# arduino_board.net
KiCad netlist of a schematic drawn in EAGLE
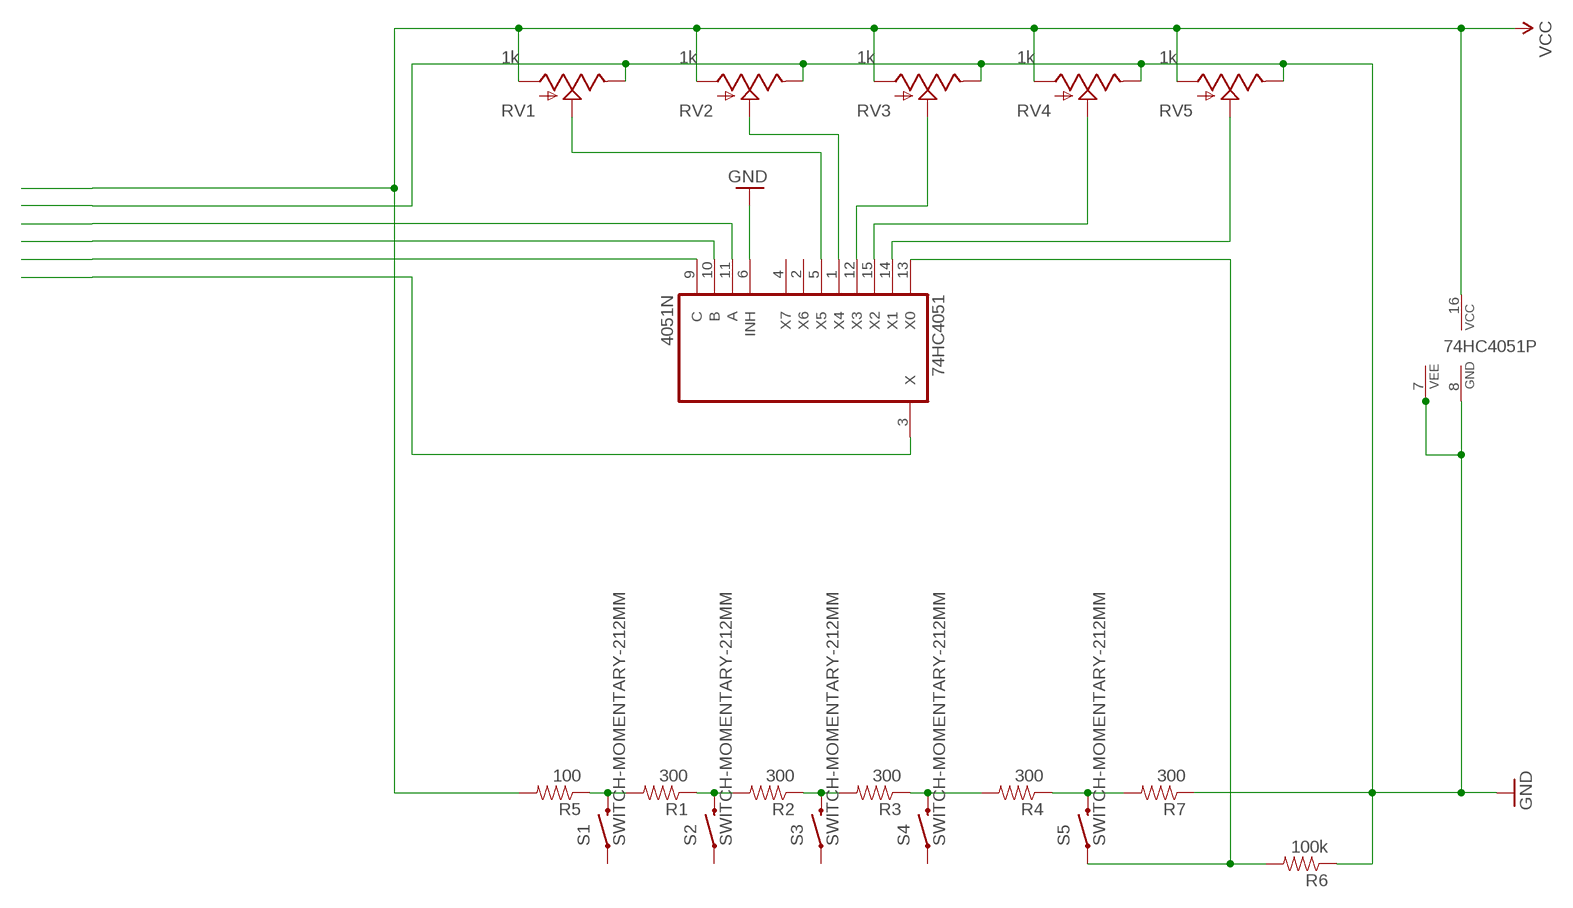
[diagram p0: schematic, sheet 1]
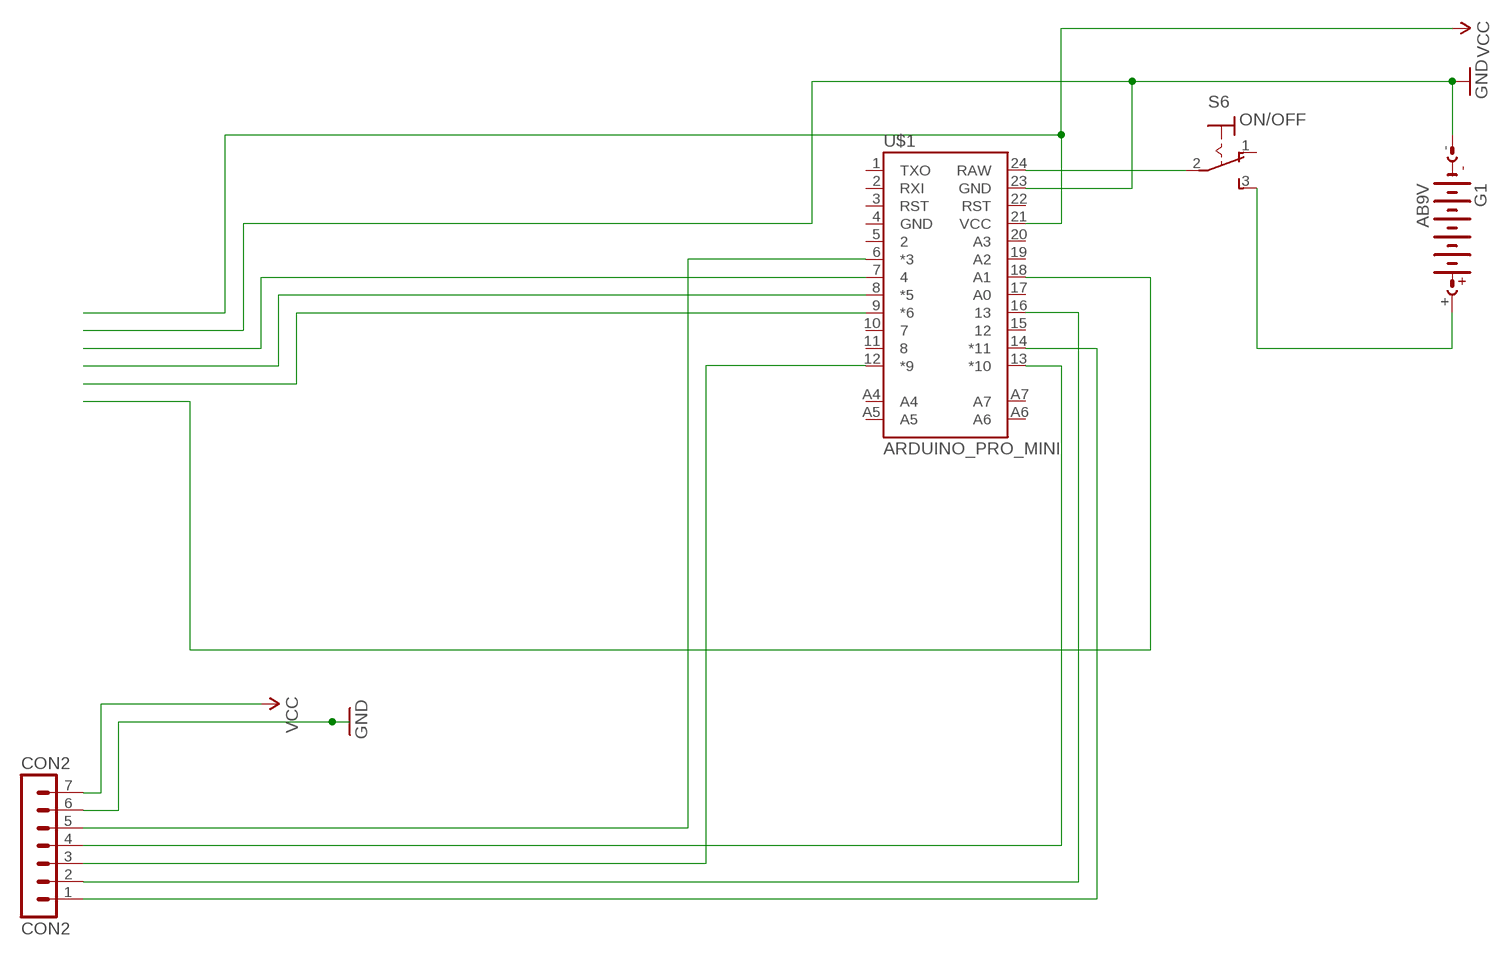
[diagram p1: schematic, sheet 2]

(export (version "E")
  (design (tool "Eeschema 10.0.6"))
  (components
    (comp (ref "CON2")
      (value "CON2")
      (footprint "eagle-import:MA07-1")
      (libsource (lib "eagle-import") (part "MA07-1"))
    )
    (comp (ref "G1")
      (value "AB9V")
      (footprint "eagle-import:AB9V")
      (libsource (lib "eagle-import") (part "AB9V"))
    )
    (comp (ref "S6")
      (value "ON/OFF")
      (footprint "eagle-import:320-916")
      (libsource (lib "eagle-import") (part "320-916"))
    )
    (comp (ref "U$1")
      (value "ARDUINO_PRO_MINI")
      (footprint "eagle-import:ARDUINO_PRO_MINI")
      (libsource (lib "eagle-import") (part "ARDUINO_PRO_MINI"))
    )
    (comp (ref "74HC4051")
      (value "4051N")
      (footprint "eagle-import:DIL16")
      (libsource (lib "eagle-import") (part "4051N"))
    )
    (comp (ref "R1")
      (value "300")
      (footprint "eagle-import:AXIAL-0.5")
      (libsource (lib "eagle-import") (part "RESISTORPTH-1/2W"))
    )
    (comp (ref "R2")
      (value "300")
      (footprint "eagle-import:AXIAL-0.5")
      (libsource (lib "eagle-import") (part "RESISTORPTH-1/2W"))
    )
    (comp (ref "R3")
      (value "300")
      (footprint "eagle-import:AXIAL-0.5")
      (libsource (lib "eagle-import") (part "RESISTORPTH-1/2W"))
    )
    (comp (ref "R4")
      (value "300")
      (footprint "eagle-import:AXIAL-0.5")
      (libsource (lib "eagle-import") (part "RESISTORPTH-1/2W"))
    )
    (comp (ref "R5")
      (value "100")
      (footprint "eagle-import:AXIAL-0.5")
      (libsource (lib "eagle-import") (part "RESISTORPTH-1/2W"))
    )
    (comp (ref "R6")
      (value "100k")
      (footprint "eagle-import:AXIAL-0.5")
      (libsource (lib "eagle-import") (part "RESISTORPTH-1/2W"))
    )
    (comp (ref "R7")
      (value "300")
      (footprint "eagle-import:AXIAL-0.5")
      (libsource (lib "eagle-import") (part "RESISTORPTH-1/2W"))
    )
    (comp (ref "RV1")
      (value "1k")
      (footprint "eagle-import:ALPS_POT")
      (libsource (lib "eagle-import") (part "POT"))
    )
    (comp (ref "RV2")
      (value "1k")
      (footprint "eagle-import:ALPS_POT")
      (libsource (lib "eagle-import") (part "POT"))
    )
    (comp (ref "RV3")
      (value "1k")
      (footprint "eagle-import:ALPS_POT")
      (libsource (lib "eagle-import") (part "POT"))
    )
    (comp (ref "RV4")
      (value "1k")
      (footprint "eagle-import:ALPS_POT")
      (libsource (lib "eagle-import") (part "POT"))
    )
    (comp (ref "RV5")
      (value "1k")
      (footprint "eagle-import:ALPS_POT")
      (libsource (lib "eagle-import") (part "POT"))
    )
    (comp (ref "S1")
      (value "SWITCH-MOMENTARY-212MM")
      (footprint "eagle-import:TACTILE-PTH-12MM")
      (libsource (lib "eagle-import") (part "SWITCH-MOMENTARY-212MM"))
    )
    (comp (ref "S2")
      (value "SWITCH-MOMENTARY-212MM")
      (footprint "eagle-import:TACTILE-PTH-12MM")
      (libsource (lib "eagle-import") (part "SWITCH-MOMENTARY-212MM"))
    )
    (comp (ref "S3")
      (value "SWITCH-MOMENTARY-212MM")
      (footprint "eagle-import:TACTILE-PTH-12MM")
      (libsource (lib "eagle-import") (part "SWITCH-MOMENTARY-212MM"))
    )
    (comp (ref "S4")
      (value "SWITCH-MOMENTARY-212MM")
      (footprint "eagle-import:TACTILE-PTH-12MM")
      (libsource (lib "eagle-import") (part "SWITCH-MOMENTARY-212MM"))
    )
    (comp (ref "S5")
      (value "SWITCH-MOMENTARY-212MM")
      (footprint "eagle-import:TACTILE-PTH-12MM")
      (libsource (lib "eagle-import") (part "SWITCH-MOMENTARY-212MM"))
    )
  )
  (nets
    (net (code "1") (name "A1") (class "Default")
      (node (ref "74HC4051") (pin "3") (pinfunction "X_3") (pintype "bidirectional"))
      (node (ref "U$1") (pin "18") (pinfunction "A1_18") (pintype "bidirectional"))
    )
    (net (code "2") (name "D4_A_S0") (class "Default")
      (node (ref "74HC4051") (pin "11") (pinfunction "A_11") (pintype "input"))
      (node (ref "U$1") (pin "7") (pinfunction "4_7") (pintype "bidirectional"))
    )
    (net (code "3") (name "D5_B_S1") (class "Default")
      (node (ref "74HC4051") (pin "10") (pinfunction "B_10") (pintype "input"))
      (node (ref "U$1") (pin "8") (pinfunction "*5_8") (pintype "bidirectional"))
    )
    (net (code "4") (name "D6_C_S2") (class "Default")
      (node (ref "74HC4051") (pin "9") (pinfunction "C_9") (pintype "input"))
      (node (ref "U$1") (pin "9") (pinfunction "*6_9") (pintype "bidirectional"))
    )
    (net (code "5") (name "GND") (class "Default")
      (node (ref "74HC4051") (pin "6") (pinfunction "INH_6") (pintype "input"))
      (node (ref "74HC4051") (pin "7") (pinfunction "VEE_7") (pintype "power_in"))
      (node (ref "74HC4051") (pin "8") (pinfunction "GND_8") (pintype "power_in"))
      (node (ref "CON2") (pin "6") (pinfunction "6_6") (pintype "passive"))
      (node (ref "G1") (pin "-") (pinfunction "-_-") (pintype "passive"))
      (node (ref "R6") (pin "P$1") (pinfunction "1_P$1") (pintype "passive"))
      (node (ref "R7") (pin "P$1") (pinfunction "1_P$1") (pintype "passive"))
      (node (ref "RV1") (pin "P$1") (pinfunction "E_P$1") (pintype "passive"))
      (node (ref "RV2") (pin "P$1") (pinfunction "E_P$1") (pintype "passive"))
      (node (ref "RV3") (pin "P$1") (pinfunction "E_P$1") (pintype "passive"))
      (node (ref "RV4") (pin "P$1") (pinfunction "E_P$1") (pintype "passive"))
      (node (ref "RV5") (pin "P$1") (pinfunction "E_P$1") (pintype "passive"))
      (node (ref "U$1") (pin "23") (pinfunction "GND_23") (pintype "bidirectional"))
    )
    (net (code "6") (name "Net-(74HC4051A-X0)") (class "Default")
      (node (ref "74HC4051") (pin "13") (pinfunction "X0_13") (pintype "bidirectional"))
      (node (ref "R6") (pin "P$2") (pinfunction "2_P$2") (pintype "passive"))
      (node (ref "S5") (pin "1") (pinfunction "1_1") (pintype "passive"))
    )
    (net (code "7") (name "Net-(74HC4051A-X1)") (class "Default")
      (node (ref "74HC4051") (pin "14") (pinfunction "X1_14") (pintype "bidirectional"))
      (node (ref "RV5") (pin "P$2") (pinfunction "S_P$2") (pintype "passive"))
    )
    (net (code "8") (name "Net-(74HC4051A-X2)") (class "Default")
      (node (ref "74HC4051") (pin "15") (pinfunction "X2_15") (pintype "bidirectional"))
      (node (ref "RV4") (pin "P$2") (pinfunction "S_P$2") (pintype "passive"))
    )
    (net (code "9") (name "Net-(74HC4051A-X3)") (class "Default")
      (node (ref "74HC4051") (pin "12") (pinfunction "X3_12") (pintype "bidirectional"))
      (node (ref "RV3") (pin "P$2") (pinfunction "S_P$2") (pintype "passive"))
    )
    (net (code "10") (name "Net-(74HC4051A-X4)") (class "Default")
      (node (ref "74HC4051") (pin "1") (pinfunction "X4_1") (pintype "bidirectional"))
      (node (ref "RV2") (pin "P$2") (pinfunction "S_P$2") (pintype "passive"))
    )
    (net (code "11") (name "Net-(74HC4051A-X5)") (class "Default")
      (node (ref "74HC4051") (pin "5") (pinfunction "X5_5") (pintype "bidirectional"))
      (node (ref "RV1") (pin "P$2") (pinfunction "S_P$2") (pintype "passive"))
    )
    (net (code "12") (name "Net-(R1-1)") (class "Default")
      (node (ref "R1") (pin "P$1") (pinfunction "1_P$1") (pintype "passive"))
      (node (ref "R2") (pin "P$2") (pinfunction "2_P$2") (pintype "passive"))
      (node (ref "S2") (pin "3") (pinfunction "2_3") (pintype "passive"))
    )
    (net (code "13") (name "Net-(R1-2)") (class "Default")
      (node (ref "R1") (pin "P$2") (pinfunction "2_P$2") (pintype "passive"))
      (node (ref "R5") (pin "P$1") (pinfunction "1_P$1") (pintype "passive"))
      (node (ref "S1") (pin "3") (pinfunction "2_3") (pintype "passive"))
    )
    (net (code "14") (name "Net-(R2-1)") (class "Default")
      (node (ref "R2") (pin "P$1") (pinfunction "1_P$1") (pintype "passive"))
      (node (ref "R3") (pin "P$2") (pinfunction "2_P$2") (pintype "passive"))
      (node (ref "S3") (pin "3") (pinfunction "2_3") (pintype "passive"))
    )
    (net (code "15") (name "Net-(R3-1)") (class "Default")
      (node (ref "R3") (pin "P$1") (pinfunction "1_P$1") (pintype "passive"))
      (node (ref "R4") (pin "P$2") (pinfunction "2_P$2") (pintype "passive"))
      (node (ref "S4") (pin "3") (pinfunction "2_3") (pintype "passive"))
    )
    (net (code "16") (name "Net-(R4-1)") (class "Default")
      (node (ref "R4") (pin "P$1") (pinfunction "1_P$1") (pintype "passive"))
      (node (ref "R7") (pin "P$2") (pinfunction "2_P$2") (pintype "passive"))
      (node (ref "S5") (pin "3") (pinfunction "2_3") (pintype "passive"))
    )
    (net (code "17") (name "Net-(S6-P)") (class "Default")
      (node (ref "S6") (pin "2") (pinfunction "P_2") (pintype "passive"))
      (node (ref "U$1") (pin "24") (pinfunction "RAW_24") (pintype "bidirectional"))
    )
    (net (code "18") (name "Net-(S6-S)") (class "Default")
      (node (ref "G1") (pin "+") (pinfunction "+_+") (pintype "passive"))
      (node (ref "S6") (pin "3") (pinfunction "S_3") (pintype "passive"))
    )
    (net (code "19") (name "Net-(U$1-*3)") (class "Default")
      (node (ref "CON2") (pin "5") (pinfunction "5_5") (pintype "passive"))
      (node (ref "U$1") (pin "6") (pinfunction "*3_6") (pintype "bidirectional"))
    )
    (net (code "20") (name "Net-(U$1-*9)") (class "Default")
      (node (ref "CON2") (pin "3") (pinfunction "3_3") (pintype "passive"))
      (node (ref "U$1") (pin "12") (pinfunction "*9_12") (pintype "bidirectional"))
    )
    (net (code "21") (name "Net-(U$1-*10)") (class "Default")
      (node (ref "CON2") (pin "4") (pinfunction "4_4") (pintype "passive"))
      (node (ref "U$1") (pin "13") (pinfunction "*10_13") (pintype "bidirectional"))
    )
    (net (code "22") (name "Net-(U$1-*11)") (class "Default")
      (node (ref "CON2") (pin "1") (pinfunction "1_1") (pintype "passive"))
      (node (ref "U$1") (pin "14") (pinfunction "*11_14") (pintype "bidirectional"))
    )
    (net (code "23") (name "Net-(U$1-13)") (class "Default")
      (node (ref "CON2") (pin "2") (pinfunction "2_2") (pintype "passive"))
      (node (ref "U$1") (pin "16") (pinfunction "13_16") (pintype "bidirectional"))
    )
    (net (code "24") (name "VCC") (class "Default")
      (node (ref "74HC4051") (pin "16") (pinfunction "VCC_16") (pintype "power_in"))
      (node (ref "CON2") (pin "7") (pinfunction "7_7") (pintype "passive"))
      (node (ref "R5") (pin "P$2") (pinfunction "2_P$2") (pintype "passive"))
      (node (ref "RV1") (pin "P$3") (pinfunction "A_P$3") (pintype "passive"))
      (node (ref "RV2") (pin "P$3") (pinfunction "A_P$3") (pintype "passive"))
      (node (ref "RV3") (pin "P$3") (pinfunction "A_P$3") (pintype "passive"))
      (node (ref "RV4") (pin "P$3") (pinfunction "A_P$3") (pintype "passive"))
      (node (ref "RV5") (pin "P$3") (pinfunction "A_P$3") (pintype "passive"))
      (node (ref "U$1") (pin "21") (pinfunction "VCC_21") (pintype "bidirectional"))
    )
    (net (code "25") (name "unconnected-(74HC4051A-X6-Pad2)") (class "Default")
      (node (ref "74HC4051") (pin "2") (pinfunction "X6_2") (pintype "bidirectional"))
    )
    (net (code "26") (name "unconnected-(74HC4051A-X7-Pad4)") (class "Default")
      (node (ref "74HC4051") (pin "4") (pinfunction "X7_4") (pintype "bidirectional"))
    )
    (net (code "27") (name "unconnected-(S1-Pad1)") (class "Default")
      (node (ref "S1") (pin "1") (pinfunction "1_1") (pintype "passive"))
    )
    (net (code "28") (name "unconnected-(S2-Pad1)") (class "Default")
      (node (ref "S2") (pin "1") (pinfunction "1_1") (pintype "passive"))
    )
    (net (code "29") (name "unconnected-(S3-Pad1)") (class "Default")
      (node (ref "S3") (pin "1") (pinfunction "1_1") (pintype "passive"))
    )
    (net (code "30") (name "unconnected-(S4-Pad1)") (class "Default")
      (node (ref "S4") (pin "1") (pinfunction "1_1") (pintype "passive"))
    )
    (net (code "31") (name "unconnected-(S6-O-Pad1)") (class "Default")
      (node (ref "S6") (pin "1") (pinfunction "O_1") (pintype "passive"))
    )
    (net (code "32") (name "unconnected-(U$1-2-Pad5)") (class "Default")
      (node (ref "U$1") (pin "5") (pinfunction "2_5") (pintype "bidirectional"))
    )
    (net (code "33") (name "unconnected-(U$1-7-Pad10)") (class "Default")
      (node (ref "U$1") (pin "10") (pinfunction "7_10") (pintype "bidirectional"))
    )
    (net (code "34") (name "unconnected-(U$1-8-Pad11)") (class "Default")
      (node (ref "U$1") (pin "11") (pinfunction "8_11") (pintype "bidirectional"))
    )
    (net (code "35") (name "unconnected-(U$1-12-Pad15)") (class "Default")
      (node (ref "U$1") (pin "15") (pinfunction "12_15") (pintype "bidirectional"))
    )
    (net (code "36") (name "unconnected-(U$1-A0-Pad17)") (class "Default")
      (node (ref "U$1") (pin "17") (pinfunction "A0_17") (pintype "bidirectional"))
    )
    (net (code "37") (name "unconnected-(U$1-A2-Pad19)") (class "Default")
      (node (ref "U$1") (pin "19") (pinfunction "A2_19") (pintype "bidirectional"))
    )
    (net (code "38") (name "unconnected-(U$1-A3-Pad20)") (class "Default")
      (node (ref "U$1") (pin "20") (pinfunction "A3_20") (pintype "bidirectional"))
    )
    (net (code "39") (name "unconnected-(U$1-GND-Pad4)") (class "Default")
      (node (ref "U$1") (pin "4") (pinfunction "GND_4") (pintype "bidirectional"))
    )
    (net (code "40") (name "unconnected-(U$1-PadA4)") (class "Default")
      (node (ref "U$1") (pin "A4") (pinfunction "A4_A4") (pintype "bidirectional"))
    )
    (net (code "41") (name "unconnected-(U$1-PadA5)") (class "Default")
      (node (ref "U$1") (pin "A5") (pinfunction "A5_A5") (pintype "bidirectional"))
    )
    (net (code "42") (name "unconnected-(U$1-PadA6)") (class "Default")
      (node (ref "U$1") (pin "A6") (pinfunction "A6_A6") (pintype "bidirectional"))
    )
    (net (code "43") (name "unconnected-(U$1-PadA7)") (class "Default")
      (node (ref "U$1") (pin "A7") (pinfunction "A7_A7") (pintype "bidirectional"))
    )
    (net (code "44") (name "unconnected-(U$1-RST-Pad3)") (class "Default")
      (node (ref "U$1") (pin "3") (pinfunction "RST_3") (pintype "bidirectional"))
    )
    (net (code "45") (name "unconnected-(U$1-RST-Pad22)") (class "Default")
      (node (ref "U$1") (pin "22") (pinfunction "RST_22") (pintype "bidirectional"))
    )
    (net (code "46") (name "unconnected-(U$1-RXI-Pad2)") (class "Default")
      (node (ref "U$1") (pin "2") (pinfunction "RXI_2") (pintype "bidirectional"))
    )
    (net (code "47") (name "unconnected-(U$1-TXO-Pad1)") (class "Default")
      (node (ref "U$1") (pin "1") (pinfunction "TXO_1") (pintype "bidirectional"))
    )
  )
)
